# MCU.net
KiCad netlist of a schematic drawn in Altium Designer
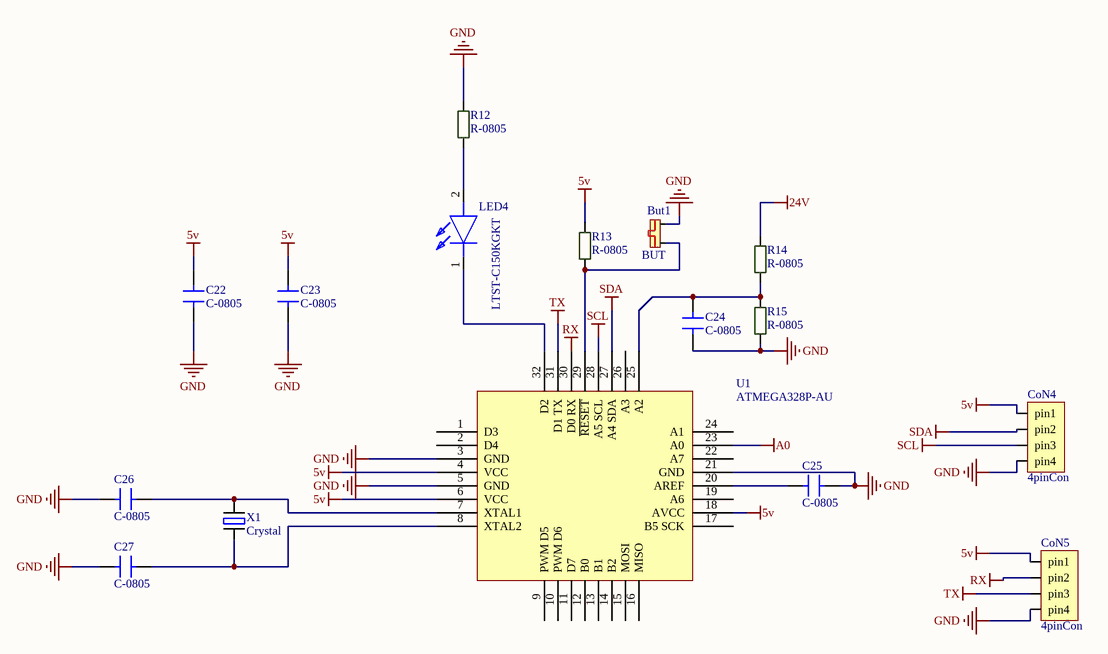
[diagram p0: MCU.SchDoc]

(export (version "E")
  (design (tool "Eeschema 10.0.6"))
  (components
    (comp (ref "But1") (value "BUT") (footprint "ButTON") (libsource (lib "Schlib2") (part "BUT")))
    (comp (ref "C22") (value "C-0805") (footprint "C-0805W") (libsource (lib "Schlib2") (part "C-0805")))
    (comp (ref "C23") (value "C-0805") (footprint "C-0805W") (libsource (lib "Schlib2") (part "C-0805")))
    (comp (ref "C24") (value "C-0805") (footprint "C-0805W") (libsource (lib "Schlib2") (part "C-0805")))
    (comp (ref "C25") (value "C-0805") (footprint "C-0805W") (libsource (lib "Schlib2") (part "C-0805")))
    (comp (ref "C26") (value "C-0805") (footprint "C-0805W") (libsource (lib "Schlib2") (part "C-0805")))
    (comp (ref "C27") (value "C-0805") (footprint "C-0805W") (libsource (lib "Schlib2") (part "C-0805")))
    (comp (ref "CoN4") (value "4pinCon") (footprint "4pinCon") (libsource (lib "Schlib1") (part "4pinCon")))
    (comp (ref "CoN5") (value "4pinCon") (footprint "4pinCon") (libsource (lib "Schlib1") (part "4pinCon")))
    (comp (ref "LED4")
      (value "LTST-C150KGKT")
      (footprint "LED1206")
      (description "LED")
      (fields
        (field (name "MOUSER PART NUMBER") "859-LTST-C150KGKT")
        (field (name "RS PART NUMBER") "6920871")
      )
      (libsource (lib "Charger_SCHLIB") (part "LTST-C150KGKT"))
    )
    (comp (ref "R12") (value "R-0805") (footprint "R-0805W") (libsource (lib "Schlib2") (part "R-0805")))
    (comp (ref "R13") (value "R-0805") (footprint "R-0805W") (libsource (lib "Schlib2") (part "R-0805")))
    (comp (ref "R14") (value "R-0805") (footprint "R-0805W") (libsource (lib "Schlib2") (part "R-0805")))
    (comp (ref "R15") (value "R-0805") (footprint "R-0805W") (libsource (lib "Schlib2") (part "R-0805")))
    (comp (ref "U1")
      (value "ATMEGA328P-AU")
      (footprint "TQFP80P900X900X120-32N")
      (description "Microchip Technology ATMEGA328P-AN, 8bit AVR Microcontroller, 20MHz, 32 kB Flash, 32-Pin TQFP")
      (libsource (lib "Schlib2") (part "ATMEGA328P-AU"))
    )
    (comp (ref "X1")
      (value "Crystal")
      (footprint "crystal")
      (description "AS49SD-16M-FC160F3-TR")
      (libsource (lib "Schlib2") (part "Crystal"))
    )
  )
  (nets
    (net (code "1") (name "5v") (class "Default")
      (node (ref "C22") (pin "2") (pinfunction "2_2") (pintype "passive"))
      (node (ref "C23") (pin "2") (pinfunction "2_2") (pintype "passive"))
      (node (ref "CoN4") (pin "1") (pinfunction "pin1_1") (pintype "passive"))
      (node (ref "CoN5") (pin "1") (pinfunction "pin1_1") (pintype "passive"))
      (node (ref "R13") (pin "2") (pinfunction "2_2") (pintype "passive"))
      (node (ref "U1") (pin "18") (pinfunction "AVCC_18") (pintype "passive"))
      (node (ref "U1") (pin "4") (pinfunction "VCC_4") (pintype "passive"))
      (node (ref "U1") (pin "6") (pinfunction "VCC_6") (pintype "passive"))
    )
    (net (code "2") (name "24V") (class "Default")
      (node (ref "R14") (pin "2") (pinfunction "2_2") (pintype "passive"))
    )
    (net (code "3") (name "A0") (class "Default")
      (node (ref "U1") (pin "23") (pinfunction "A0_23") (pintype "passive"))
    )
    (net (code "4") (name "GND") (class "Default")
      (node (ref "But1") (pin "2") (pinfunction "2_2") (pintype "passive"))
      (node (ref "C22") (pin "1") (pinfunction "1_1") (pintype "passive"))
      (node (ref "C23") (pin "1") (pinfunction "1_1") (pintype "passive"))
      (node (ref "C24") (pin "1") (pinfunction "1_1") (pintype "passive"))
      (node (ref "C25") (pin "2") (pinfunction "2_2") (pintype "passive"))
      (node (ref "C26") (pin "1") (pinfunction "1_1") (pintype "passive"))
      (node (ref "C27") (pin "1") (pinfunction "1_1") (pintype "passive"))
      (node (ref "CoN4") (pin "4") (pinfunction "pin4_4") (pintype "passive"))
      (node (ref "CoN5") (pin "4") (pinfunction "pin4_4") (pintype "passive"))
      (node (ref "R12") (pin "2") (pinfunction "2_2") (pintype "passive"))
      (node (ref "R15") (pin "1") (pinfunction "1_1") (pintype "passive"))
      (node (ref "U1") (pin "21") (pinfunction "GND_21") (pintype "passive"))
      (node (ref "U1") (pin "3") (pinfunction "GND_3") (pintype "passive"))
      (node (ref "U1") (pin "5") (pinfunction "GND_5") (pintype "passive"))
    )
    (net (code "5") (name "Net-(LED4-A)") (class "Default")
      (node (ref "LED4") (pin "2") (pinfunction "A_2") (pintype "passive"))
      (node (ref "R12") (pin "1") (pinfunction "1_1") (pintype "passive"))
    )
    (net (code "6") (name "Net-(LED4-K)") (class "Default")
      (node (ref "LED4") (pin "1") (pinfunction "K_1") (pintype "passive"))
      (node (ref "U1") (pin "32") (pinfunction "D2_32") (pintype "passive"))
    )
    (net (code "7") (name "Net-(U1-A2)") (class "Default")
      (node (ref "C24") (pin "2") (pinfunction "2_2") (pintype "passive"))
      (node (ref "R14") (pin "1") (pinfunction "1_1") (pintype "passive"))
      (node (ref "R15") (pin "2") (pinfunction "2_2") (pintype "passive"))
      (node (ref "U1") (pin "25") (pinfunction "A2_25") (pintype "passive"))
    )
    (net (code "8") (name "Net-(U1-AREF)") (class "Default")
      (node (ref "C25") (pin "1") (pinfunction "1_1") (pintype "passive"))
      (node (ref "U1") (pin "20") (pinfunction "AREF_20") (pintype "passive"))
    )
    (net (code "9") (name "Net-(U1-XTAL1)") (class "Default")
      (node (ref "C26") (pin "2") (pinfunction "2_2") (pintype "passive"))
      (node (ref "U1") (pin "7") (pinfunction "XTAL1_7") (pintype "passive"))
      (node (ref "X1") (pin "1") (pinfunction "1_1") (pintype "passive"))
    )
    (net (code "10") (name "Net-(U1-XTAL2)") (class "Default")
      (node (ref "C27") (pin "2") (pinfunction "2_2") (pintype "passive"))
      (node (ref "U1") (pin "8") (pinfunction "XTAL2_8") (pintype "passive"))
      (node (ref "X1") (pin "2") (pinfunction "2_2") (pintype "passive"))
    )
    (net (code "11") (name "Net-(U1-~{RESET})") (class "Default")
      (node (ref "But1") (pin "1") (pinfunction "1_1") (pintype "passive"))
      (node (ref "R13") (pin "1") (pinfunction "1_1") (pintype "passive"))
      (node (ref "U1") (pin "29") (pinfunction "~{RESET}_29") (pintype "passive"))
    )
    (net (code "12") (name "RX") (class "Default")
      (node (ref "CoN5") (pin "2") (pinfunction "pin2_2") (pintype "passive"))
      (node (ref "U1") (pin "30") (pinfunction "D0_RX_30") (pintype "passive"))
    )
    (net (code "13") (name "SCL") (class "Default")
      (node (ref "CoN4") (pin "3") (pinfunction "pin3_3") (pintype "passive"))
      (node (ref "U1") (pin "28") (pinfunction "A5_SCL_28") (pintype "passive"))
    )
    (net (code "14") (name "SDA") (class "Default")
      (node (ref "CoN4") (pin "2") (pinfunction "pin2_2") (pintype "passive"))
      (node (ref "U1") (pin "27") (pinfunction "A4_SDA_27") (pintype "passive"))
    )
    (net (code "15") (name "TX") (class "Default")
      (node (ref "CoN5") (pin "3") (pinfunction "pin3_3") (pintype "passive"))
      (node (ref "U1") (pin "31") (pinfunction "D1_TX_31") (pintype "passive"))
    )
    (net (code "16") (name "unconnected-(U1-A1-Pad24)") (class "Default")
      (node (ref "U1") (pin "24") (pinfunction "A1_24") (pintype "passive"))
    )
    (net (code "17") (name "unconnected-(U1-A3-Pad26)") (class "Default")
      (node (ref "U1") (pin "26") (pinfunction "A3_26") (pintype "passive"))
    )
    (net (code "18") (name "unconnected-(U1-A6-Pad19)") (class "Default")
      (node (ref "U1") (pin "19") (pinfunction "A6_19") (pintype "passive"))
    )
    (net (code "19") (name "unconnected-(U1-A7-Pad22)") (class "Default")
      (node (ref "U1") (pin "22") (pinfunction "A7_22") (pintype "passive"))
    )
    (net (code "20") (name "unconnected-(U1-B0-Pad12)") (class "Default")
      (node (ref "U1") (pin "12") (pinfunction "B0_12") (pintype "passive"))
    )
    (net (code "21") (name "unconnected-(U1-B1-Pad13)") (class "Default")
      (node (ref "U1") (pin "13") (pinfunction "B1_13") (pintype "passive"))
    )
    (net (code "22") (name "unconnected-(U1-B2-Pad14)") (class "Default")
      (node (ref "U1") (pin "14") (pinfunction "B2_14") (pintype "passive"))
    )
    (net (code "23") (name "unconnected-(U1-B5_SCK-Pad17)") (class "Default")
      (node (ref "U1") (pin "17") (pinfunction "B5_SCK_17") (pintype "passive"))
    )
    (net (code "24") (name "unconnected-(U1-D3-Pad1)") (class "Default")
      (node (ref "U1") (pin "1") (pinfunction "D3_1") (pintype "passive"))
    )
    (net (code "25") (name "unconnected-(U1-D4-Pad2)") (class "Default")
      (node (ref "U1") (pin "2") (pinfunction "D4_2") (pintype "passive"))
    )
    (net (code "26") (name "unconnected-(U1-D7-Pad11)") (class "Default")
      (node (ref "U1") (pin "11") (pinfunction "D7_11") (pintype "passive"))
    )
    (net (code "27") (name "unconnected-(U1-MISO-Pad16)") (class "Default")
      (node (ref "U1") (pin "16") (pinfunction "MISO_16") (pintype "passive"))
    )
    (net (code "28") (name "unconnected-(U1-MOSI-Pad15)") (class "Default")
      (node (ref "U1") (pin "15") (pinfunction "MOSI_15") (pintype "passive"))
    )
    (net (code "29") (name "unconnected-(U1-PWM_D5-Pad9)") (class "Default")
      (node (ref "U1") (pin "9") (pinfunction "PWM_D5_9") (pintype "passive"))
    )
    (net (code "30") (name "unconnected-(U1-PWM_D6-Pad10)") (class "Default")
      (node (ref "U1") (pin "10") (pinfunction "PWM_D6_10") (pintype "passive"))
    )
  )
)
